# trinamic-controller-dribbler.net
KiCad netlist of a schematic drawn in Altium Designer
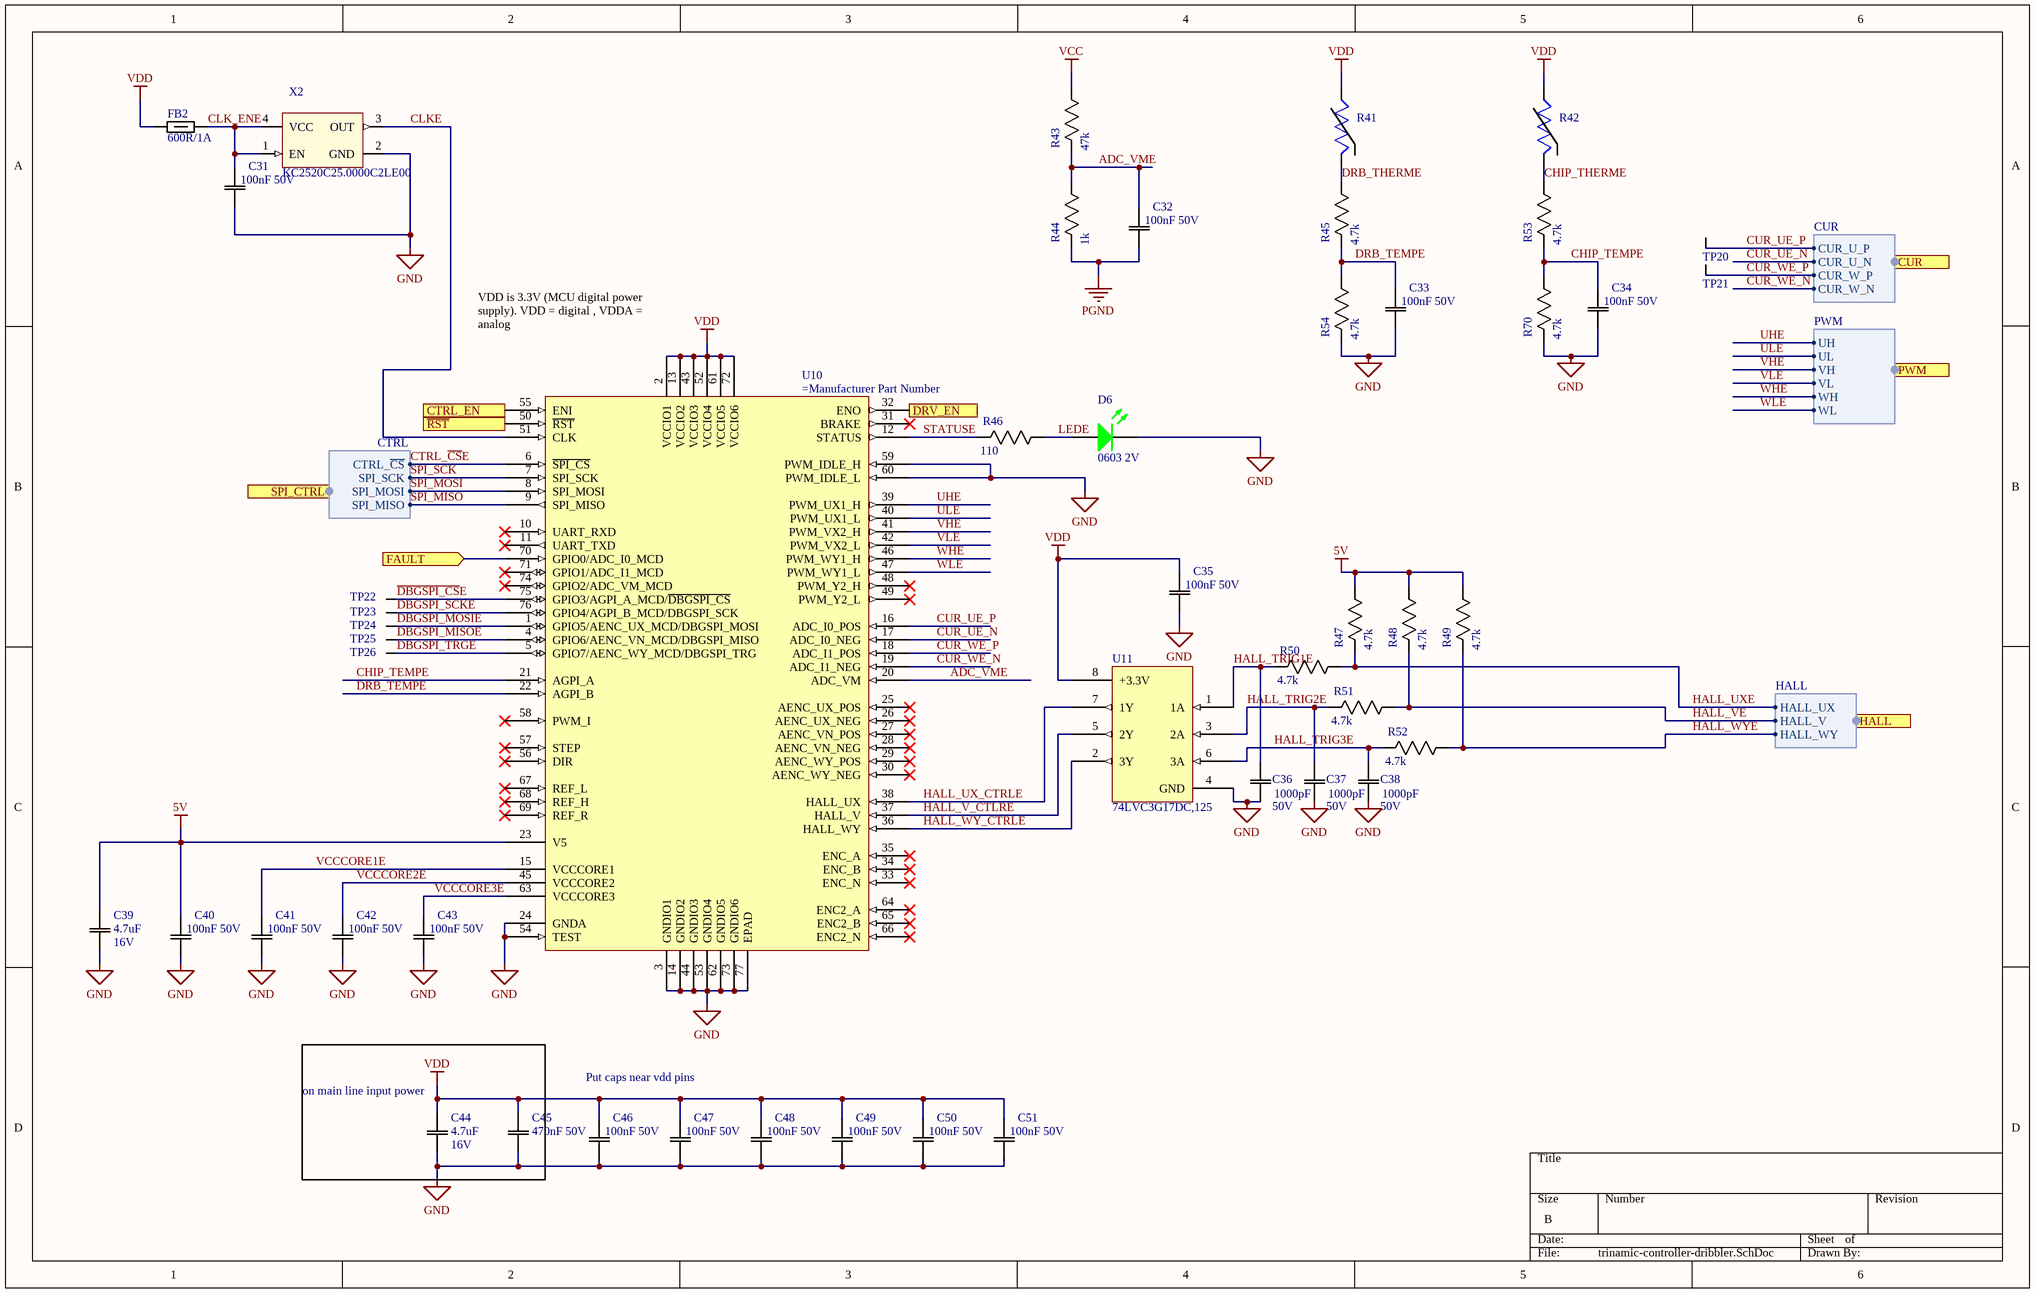
[diagram p0: trinamic-controller-dribbler.SchDoc]

(export (version "E")
  (design (tool "Eeschema 10.0.6"))
  (components
    (comp (ref "C31")
      (value "100nF 50V")
      (footprint "0603")
      (description "Default Symbol for Capacitors")
      (fields (field (name "TOLERANCE") "10%") (field (name "PART NUMBER") "CAP 100nF 50V"))
      (libsource (lib "capacitor_library") (part "CAP_Default"))
    )
    (comp (ref "C32")
      (value "100nF 50V")
      (footprint "0603")
      (description "Default Symbol for Capacitors")
      (fields (field (name "TOLERANCE") "10%") (field (name "PART NUMBER") "CAP 100nF 50V"))
      (libsource (lib "capacitor_library") (part "CAP_Default"))
    )
    (comp (ref "C33")
      (value "100nF 50V")
      (footprint "0603")
      (description "Default Symbol for Capacitors")
      (fields (field (name "TOLERANCE") "10%") (field (name "PART NUMBER") "CAP 100nF 50V"))
      (libsource (lib "capacitor_library") (part "CAP_Default"))
    )
    (comp (ref "C34")
      (value "100nF 50V")
      (footprint "0603")
      (description "Default Symbol for Capacitors")
      (fields (field (name "TOLERANCE") "10%") (field (name "PART NUMBER") "CAP 100nF 50V"))
      (libsource (lib "capacitor_library") (part "CAP_Default"))
    )
    (comp (ref "C35")
      (value "100nF 50V")
      (footprint "0603")
      (description "Default Symbol for Capacitors")
      (fields (field (name "TOLERANCE") "10%") (field (name "PART NUMBER") "CAP 100nF 50V"))
      (libsource (lib "capacitor_library") (part "CAP_Default"))
    )
    (comp (ref "C36")
      (value "1000pF")
      (footprint "0603")
      (description "Default Symbol for Capacitors")
      (fields
        (field (name "TOLERANCE") "10%")
        (field (name "RATING") "50V")
        (field (name "PART NUMBER") "CAP 1000pF 50V")
      )
      (libsource (lib "capacitor_library") (part "CAP_Default"))
    )
    (comp (ref "C37")
      (value "1000pF")
      (footprint "0603")
      (description "Default Symbol for Capacitors")
      (fields
        (field (name "TOLERANCE") "10%")
        (field (name "RATING") "50V")
        (field (name "PART NUMBER") "CAP 1000pF 50V")
      )
      (libsource (lib "capacitor_library") (part "CAP_Default"))
    )
    (comp (ref "C38")
      (value "1000pF")
      (footprint "0603")
      (description "Default Symbol for Capacitors")
      (fields
        (field (name "TOLERANCE") "10%")
        (field (name "RATING") "50V")
        (field (name "PART NUMBER") "CAP 1000pF 50V")
      )
      (libsource (lib "capacitor_library") (part "CAP_Default"))
    )
    (comp (ref "C39")
      (value "4.7uF")
      (footprint "0603")
      (description "Default Symbol for Capacitors")
      (fields
        (field (name "TOLERANCE") "10%")
        (field (name "RATING") "16V")
        (field (name "PART NUMBER") "CAP 4.7uF 16V")
      )
      (libsource (lib "capacitor_library") (part "CAP_Default"))
    )
    (comp (ref "C40")
      (value "100nF 50V")
      (footprint "0603")
      (description "Default Symbol for Capacitors")
      (fields (field (name "TOLERANCE") "10%") (field (name "PART NUMBER") "CAP 100nF 50V"))
      (libsource (lib "capacitor_library") (part "CAP_Default"))
    )
    (comp (ref "C41")
      (value "100nF 50V")
      (footprint "0603")
      (description "Default Symbol for Capacitors")
      (fields (field (name "TOLERANCE") "10%") (field (name "PART NUMBER") "CAP 100nF 50V"))
      (libsource (lib "capacitor_library") (part "CAP_Default"))
    )
    (comp (ref "C42")
      (value "100nF 50V")
      (footprint "0603")
      (description "Default Symbol for Capacitors")
      (fields (field (name "TOLERANCE") "10%") (field (name "PART NUMBER") "CAP 100nF 50V"))
      (libsource (lib "capacitor_library") (part "CAP_Default"))
    )
    (comp (ref "C43")
      (value "100nF 50V")
      (footprint "0603")
      (description "Default Symbol for Capacitors")
      (fields (field (name "TOLERANCE") "10%") (field (name "PART NUMBER") "CAP 100nF 50V"))
      (libsource (lib "capacitor_library") (part "CAP_Default"))
    )
    (comp (ref "C44")
      (value "4.7uF")
      (footprint "0603")
      (description "Default Symbol for Capacitors")
      (fields
        (field (name "TOLERANCE") "10%")
        (field (name "RATING") "16V")
        (field (name "PART NUMBER") "CAP 4.7uF 16V")
      )
      (libsource (lib "capacitor_library") (part "CAP_Default"))
    )
    (comp (ref "C45")
      (value "470nF 50V")
      (footprint "0603")
      (description "Default Symbol for Capacitors")
      (fields (field (name "TOLERANCE") "10%") (field (name "PART NUMBER") "CAP 470nF 50V"))
      (libsource (lib "capacitor_library") (part "CAP_Default"))
    )
    (comp (ref "C46")
      (value "100nF 50V")
      (footprint "0603")
      (description "Default Symbol for Capacitors")
      (fields (field (name "TOLERANCE") "10%") (field (name "PART NUMBER") "CAP 100nF 50V"))
      (libsource (lib "capacitor_library") (part "CAP_Default"))
    )
    (comp (ref "C47")
      (value "100nF 50V")
      (footprint "0603")
      (description "Default Symbol for Capacitors")
      (fields (field (name "TOLERANCE") "10%") (field (name "PART NUMBER") "CAP 100nF 50V"))
      (libsource (lib "capacitor_library") (part "CAP_Default"))
    )
    (comp (ref "C48")
      (value "100nF 50V")
      (footprint "0603")
      (description "Default Symbol for Capacitors")
      (fields (field (name "TOLERANCE") "10%") (field (name "PART NUMBER") "CAP 100nF 50V"))
      (libsource (lib "capacitor_library") (part "CAP_Default"))
    )
    (comp (ref "C49")
      (value "100nF 50V")
      (footprint "0603")
      (description "Default Symbol for Capacitors")
      (fields (field (name "TOLERANCE") "10%") (field (name "PART NUMBER") "CAP 100nF 50V"))
      (libsource (lib "capacitor_library") (part "CAP_Default"))
    )
    (comp (ref "C50")
      (value "100nF 50V")
      (footprint "0603")
      (description "Default Symbol for Capacitors")
      (fields (field (name "TOLERANCE") "10%") (field (name "PART NUMBER") "CAP 100nF 50V"))
      (libsource (lib "capacitor_library") (part "CAP_Default"))
    )
    (comp (ref "C51")
      (value "100nF 50V")
      (footprint "0603")
      (description "Default Symbol for Capacitors")
      (fields (field (name "TOLERANCE") "10%") (field (name "PART NUMBER") "CAP 100nF 50V"))
      (libsource (lib "capacitor_library") (part "CAP_Default"))
    )
    (comp (ref "D6")
      (value "0603 2V")
      (footprint "0603 - LED")
      (description "LED Uni-Color Green 574nm 2-Pin Chip LED T/R")
      (fields (field (name "PART NUMBER") "LED GREEN SMD 0603"))
      (libsource (lib "Diode_Library") (part "LED GREEN SMD 0603"))
    )
    (comp (ref "FB2")
      (value "600R/1A")
      (footprint "0603")
      (fields (field (name "PART NUMBER") "FERRITE BEAD 200 MOHM 0603 1LN"))
      (libsource (lib "Inductor_Library") (part "FERRITE BEAD 200 MOHM 0603 1LN"))
    )
    (comp (ref "R41")
      (value "RES NTC 10k")
      (footprint "THERMISTOR TH")
      (fields (field (name "PART NUMBER") "RES NTC 10k TH") (field (name "TOLERANCE") "1%"))
      (libsource (lib "Resistor_Library") (part "RES NTC 10k"))
    )
    (comp (ref "R42")
      (value "RES NTC 10k")
      (footprint "0603")
      (fields (field (name "PART NUMBER") "RES NTC 10k CHIP") (field (name "TOLERANCE") "1%"))
      (libsource (lib "Resistor_Library") (part "RES NTC 10k"))
    )
    (comp (ref "R43")
      (value "47k")
      (footprint "0603")
      (description "Default Resistor Symbol")
      (fields (field (name "TOLERANCE") "1%") (field (name "PART NUMBER") "RES 47k 1/8W - 1%"))
      (libsource (lib "") (part "RES_DEFAULT_2"))
    )
    (comp (ref "R44")
      (value "1k")
      (footprint "0603")
      (description "Default Resistor Symbol")
      (fields (field (name "TOLERANCE") "1%") (field (name "PART NUMBER") "RES 1k 1/8W - 1%"))
      (libsource (lib "") (part "RES_DEFAULT_1"))
    )
    (comp (ref "R45")
      (value "4.7k")
      (footprint "0603")
      (description "Default Resistor Symbol")
      (fields (field (name "TOLERANCE") "1%") (field (name "PART NUMBER") "RES 4.7k 1/8W - 1%"))
      (libsource (lib "") (part "RES_DEFAULT_1"))
    )
    (comp (ref "R46")
      (value "110")
      (footprint "0603")
      (description "Default Resistor Symbol")
      (fields (field (name "TOLERANCE") "1%") (field (name "PART NUMBER") "RES 110.0 1/8W - 1%"))
      (libsource (lib "Resistor_Library") (part "RES_DEFAULT"))
    )
    (comp (ref "R47")
      (value "4.7k")
      (footprint "0603")
      (description "Default Resistor Symbol")
      (fields (field (name "TOLERANCE") "5%") (field (name "PART NUMBER") "RES 4.7k 1/8W - 5%"))
      (libsource (lib "Resistor_Library") (part "RES_DEFAULT"))
    )
    (comp (ref "R48")
      (value "4.7k")
      (footprint "0603")
      (description "Default Resistor Symbol")
      (fields (field (name "TOLERANCE") "5%") (field (name "PART NUMBER") "RES 4.7k 1/8W - 5%"))
      (libsource (lib "Resistor_Library") (part "RES_DEFAULT"))
    )
    (comp (ref "R49")
      (value "4.7k")
      (footprint "0603")
      (description "Default Resistor Symbol")
      (fields (field (name "TOLERANCE") "5%") (field (name "PART NUMBER") "RES 4.7k 1/8W - 5%"))
      (libsource (lib "") (part "RES_DEFAULT_1"))
    )
    (comp (ref "R50")
      (value "4.7k")
      (footprint "0603")
      (description "Default Resistor Symbol")
      (fields (field (name "TOLERANCE") "5%") (field (name "PART NUMBER") "RES 4.7k 1/8W - 5%"))
      (libsource (lib "Resistor_Library") (part "RES_DEFAULT"))
    )
    (comp (ref "R51")
      (value "4.7k")
      (footprint "0603")
      (description "Default Resistor Symbol")
      (fields (field (name "TOLERANCE") "5%") (field (name "PART NUMBER") "RES 4.7k 1/8W - 5%"))
      (libsource (lib "Resistor_Library") (part "RES_DEFAULT"))
    )
    (comp (ref "R52")
      (value "4.7k")
      (footprint "0603")
      (description "Default Resistor Symbol")
      (fields (field (name "TOLERANCE") "5%") (field (name "PART NUMBER") "RES 4.7k 1/8W - 5%"))
      (libsource (lib "Resistor_Library") (part "RES_DEFAULT"))
    )
    (comp (ref "R53")
      (value "4.7k")
      (footprint "0603")
      (description "Default Resistor Symbol")
      (fields (field (name "TOLERANCE") "1%") (field (name "PART NUMBER") "RES 4.7k 1/8W - 1%"))
      (libsource (lib "") (part "RES_DEFAULT_1"))
    )
    (comp (ref "R54")
      (value "4.7k")
      (footprint "0603")
      (description "Default Resistor Symbol")
      (fields (field (name "TOLERANCE") "1%") (field (name "PART NUMBER") "RES 4.7k 1/8W - 1%"))
      (libsource (lib "") (part "RES_DEFAULT_1"))
    )
    (comp (ref "R70")
      (value "4.7k")
      (footprint "0603")
      (description "Default Resistor Symbol")
      (fields (field (name "TOLERANCE") "1%") (field (name "PART NUMBER") "RES 4.7k 1/8W - 1%"))
      (libsource (lib "") (part "RES_DEFAULT_1"))
    )
    (comp (ref "TP20")
      (value "Test Point (Via)")
      (footprint "TP")
      (libsource (lib "IC_Library") (part "Test Point (Via)"))
    )
    (comp (ref "TP21")
      (value "Test Point (Via)")
      (footprint "TP")
      (libsource (lib "IC_Library") (part "Test Point (Via)"))
    )
    (comp (ref "TP22")
      (value "Test Point (Via)")
      (footprint "TP")
      (libsource (lib "IC_Library") (part "Test Point (Via)"))
    )
    (comp (ref "TP23")
      (value "Test Point (Via)")
      (footprint "TP")
      (libsource (lib "IC_Library") (part "Test Point (Via)"))
    )
    (comp (ref "TP24")
      (value "Test Point (Via)")
      (footprint "TP")
      (libsource (lib "IC_Library") (part "Test Point (Via)"))
    )
    (comp (ref "TP25")
      (value "Test Point (Via)")
      (footprint "TP")
      (libsource (lib "IC_Library") (part "Test Point (Via)"))
    )
    (comp (ref "TP26")
      (value "Test Point (Via)")
      (footprint "TP")
      (libsource (lib "IC_Library") (part "Test Point (Via)"))
    )
    (comp (ref "U10")
      (value "~")
      (footprint "QFN40P1050X650X90_HS-77N")
      (description "Motor Driver, -40 To 125Deg C Rohs Compliant: Yes")
      (fields (field (name "PART NUMBER") "TMC4671"))
      (libsource (lib "IC_Library") (part "TMC4671"))
    )
    (comp (ref "U11")
      (value "74LVC3G17DC,125")
      (footprint "8-VSSOP")
      (description "IC BUFFER TRIPLE SCHMITT TRIGGER 5.5V VSSOP-8")
      (fields (field (name "PART NUMBER") "IC 74LVC3G17DC,125"))
      (libsource (lib "IC_Library") (part "IC 74LVC3G17DC,125"))
    )
    (comp (ref "X2")
      (value "KC2520C25.0000C2LE00")
      (footprint "KC2520C25.0000C2LE00")
      (description "Oscillator XO 25MHz ±15ppm 15pF CMOS 55% 2.5V/3.3V 4-Pin Mini-CSMD T/R")
      (fields (field (name "PART NUMBER") "XTAL OSC 25MHz 3.3V"))
      (libsource (lib "Oscillator_Library") (part "XTAL OSC 25MHz 3.3V"))
    )
  )
  (nets
    (net (code "5") (name "/ADC_VME") (class "Default")
      (node (ref "C32") (pin "2") (pinfunction "C2_2") (pintype "passive"))
      (node (ref "R43") (pin "2") (pinfunction "R2_2") (pintype "passive"))
      (node (ref "R44") (pin "1") (pinfunction "R1_1") (pintype "passive"))
      (node (ref "U10") (pin "20") (pinfunction "ADC_VM_20") (pintype "input"))
    )
    (net (code "6") (name "/CHIP_TEMPE") (class "Default")
      (node (ref "C34") (pin "2") (pinfunction "C2_2") (pintype "passive"))
      (node (ref "R53") (pin "2") (pinfunction "R2_2") (pintype "passive"))
      (node (ref "R70") (pin "1") (pinfunction "R1_1") (pintype "passive"))
      (node (ref "U10") (pin "21") (pinfunction "AGPI_A_21") (pintype "input"))
    )
    (net (code "7") (name "/CHIP_THERME") (class "Default")
      (node (ref "R42") (pin "1") (pinfunction "1_1") (pintype "passive"))
      (node (ref "R53") (pin "1") (pinfunction "R1_1") (pintype "passive"))
    )
    (net (code "8") (name "/CLKE") (class "Default")
      (node (ref "U10") (pin "51") (pinfunction "CLK_51") (pintype "input"))
      (node (ref "X2") (pin "3") (pinfunction "OUT_3") (pintype "output"))
    )
    (net (code "9") (name "/CLK_ENE") (class "Default")
      (node (ref "C31") (pin "2") (pinfunction "C2_2") (pintype "passive"))
      (node (ref "FB2") (pin "2") (pinfunction "2_2") (pintype "passive"))
      (node (ref "X2") (pin "1") (pinfunction "EN_1") (pintype "input"))
      (node (ref "X2") (pin "4") (pinfunction "VCC_4") (pintype "power_in"))
    )
    (net (code "10") (name "/CTRL_EN") (class "Default")
      (node (ref "U10") (pin "55") (pinfunction "ENI_55") (pintype "input"))
    )
    (net (code "11") (name "/CTRL_~{CS}E") (class "Default")
      (node (ref "U10") (pin "6") (pinfunction "~{SPI_CS}_6") (pintype "input"))
    )
    (net (code "12") (name "/CUR_UE_N") (class "Default")
      (node (ref "U10") (pin "17") (pinfunction "ADC_I0_NEG_17") (pintype "input"))
    )
    (net (code "13") (name "/CUR_UE_P") (class "Default")
      (node (ref "TP20") (pin "1") (pinfunction "1_1") (pintype "passive"))
      (node (ref "U10") (pin "16") (pinfunction "ADC_I0_POS_16") (pintype "input"))
    )
    (net (code "14") (name "/CUR_WE_N") (class "Default")
      (node (ref "U10") (pin "19") (pinfunction "ADC_I1_NEG_19") (pintype "input"))
    )
    (net (code "15") (name "/CUR_WE_P") (class "Default")
      (node (ref "TP21") (pin "1") (pinfunction "1_1") (pintype "passive"))
      (node (ref "U10") (pin "18") (pinfunction "ADC_I1_POS_18") (pintype "input"))
    )
    (net (code "16") (name "/DBGSPI_MISOE") (class "Default")
      (node (ref "TP25") (pin "1") (pinfunction "1_1") (pintype "passive"))
      (node (ref "U10") (pin "4") (pinfunction "GPIO6/AENC_VN_MCD/DBGSPI_MISO_4") (pintype "bidirectional"))
    )
    (net (code "17") (name "/DBGSPI_MOSIE") (class "Default")
      (node (ref "TP24") (pin "1") (pinfunction "1_1") (pintype "passive"))
      (node (ref "U10") (pin "1") (pinfunction "GPIO5/AENC_UX_MCD/DBGSPI_MOSI_1") (pintype "bidirectional"))
    )
    (net (code "18") (name "/DBGSPI_SCKE") (class "Default")
      (node (ref "TP23") (pin "1") (pinfunction "1_1") (pintype "passive"))
      (node (ref "U10") (pin "76") (pinfunction "GPIO4/AGPI_B_MCD/DBGSPI_SCK_76") (pintype "bidirectional"))
    )
    (net (code "19") (name "/DBGSPI_TRGE") (class "Default")
      (node (ref "TP26") (pin "1") (pinfunction "1_1") (pintype "passive"))
      (node (ref "U10") (pin "5") (pinfunction "GPIO7/AENC_WY_MCD/DBGSPI_TRG_5") (pintype "bidirectional"))
    )
    (net (code "20") (name "/DRB_TEMPE") (class "Default")
      (node (ref "C33") (pin "2") (pinfunction "C2_2") (pintype "passive"))
      (node (ref "R45") (pin "2") (pinfunction "R2_2") (pintype "passive"))
      (node (ref "R54") (pin "1") (pinfunction "R1_1") (pintype "passive"))
      (node (ref "U10") (pin "22") (pinfunction "AGPI_B_22") (pintype "input"))
    )
    (net (code "21") (name "/DRB_THERME") (class "Default")
      (node (ref "R41") (pin "1") (pinfunction "1_1") (pintype "passive"))
      (node (ref "R45") (pin "1") (pinfunction "R1_1") (pintype "passive"))
    )
    (net (code "22") (name "/DRV_EN") (class "Default")
      (node (ref "U10") (pin "32") (pinfunction "ENO_32") (pintype "output"))
    )
    (net (code "23") (name "/FAULT") (class "Default")
      (node (ref "U10") (pin "70") (pinfunction "GPIO0/ADC_I0_MCD_70") (pintype "input"))
    )
    (net (code "24") (name "/HALL_TRIG1E") (class "Default")
      (node (ref "C36") (pin "2") (pinfunction "C2_2") (pintype "passive"))
      (node (ref "R50") (pin "2") (pinfunction "R2_2") (pintype "passive"))
      (node (ref "U11") (pin "1") (pinfunction "1A_1") (pintype "input"))
    )
    (net (code "25") (name "/HALL_TRIG2E") (class "Default")
      (node (ref "C37") (pin "2") (pinfunction "C2_2") (pintype "passive"))
      (node (ref "R51") (pin "2") (pinfunction "R2_2") (pintype "passive"))
      (node (ref "U11") (pin "3") (pinfunction "2A_3") (pintype "input"))
    )
    (net (code "26") (name "/HALL_TRIG3E") (class "Default")
      (node (ref "C38") (pin "2") (pinfunction "C2_2") (pintype "passive"))
      (node (ref "R52") (pin "2") (pinfunction "R2_2") (pintype "passive"))
      (node (ref "U11") (pin "6") (pinfunction "3A_6") (pintype "input"))
    )
    (net (code "27") (name "/HALL_UXE") (class "Default")
      (node (ref "R47") (pin "2") (pinfunction "R2_2") (pintype "passive"))
      (node (ref "R50") (pin "1") (pinfunction "R1_1") (pintype "passive"))
    )
    (net (code "28") (name "/HALL_UX_CTRLE") (class "Default")
      (node (ref "U10") (pin "38") (pinfunction "HALL_UX_38") (pintype "input"))
      (node (ref "U11") (pin "7") (pinfunction "1Y_7") (pintype "output"))
    )
    (net (code "29") (name "/HALL_VE") (class "Default")
      (node (ref "R48") (pin "2") (pinfunction "R2_2") (pintype "passive"))
      (node (ref "R51") (pin "1") (pinfunction "R1_1") (pintype "passive"))
    )
    (net (code "30") (name "/HALL_V_CTLRE") (class "Default")
      (node (ref "U10") (pin "37") (pinfunction "HALL_V_37") (pintype "input"))
      (node (ref "U11") (pin "5") (pinfunction "2Y_5") (pintype "output"))
    )
    (net (code "31") (name "/HALL_WYE") (class "Default")
      (node (ref "R49") (pin "2") (pinfunction "R2_2") (pintype "passive"))
      (node (ref "R52") (pin "1") (pinfunction "R1_1") (pintype "passive"))
    )
    (net (code "32") (name "/HALL_WY_CTRLE") (class "Default")
      (node (ref "U10") (pin "36") (pinfunction "HALL_WY_36") (pintype "input"))
      (node (ref "U11") (pin "2") (pinfunction "3Y_2") (pintype "output"))
    )
    (net (code "33") (name "/LEDE") (class "Default")
      (node (ref "D6") (pin "1") (pinfunction "A_1") (pintype "passive"))
      (node (ref "R46") (pin "1") (pinfunction "R1_1") (pintype "passive"))
    )
    (net (code "34") (name "/SPI_MISO") (class "Default")
      (node (ref "U10") (pin "9") (pinfunction "SPI_MISO_9") (pintype "output"))
    )
    (net (code "35") (name "/SPI_MOSI") (class "Default")
      (node (ref "U10") (pin "8") (pinfunction "SPI_MOSI_8") (pintype "input"))
    )
    (net (code "36") (name "/SPI_SCK") (class "Default")
      (node (ref "U10") (pin "7") (pinfunction "SPI_SCK_7") (pintype "input"))
    )
    (net (code "37") (name "/STATUSE") (class "Default")
      (node (ref "R46") (pin "2") (pinfunction "R2_2") (pintype "passive"))
      (node (ref "U10") (pin "12") (pinfunction "STATUS_12") (pintype "output"))
    )
    (net (code "38") (name "/UHE") (class "Default")
      (node (ref "U10") (pin "39") (pinfunction "PWM_UX1_H_39") (pintype "output"))
    )
    (net (code "39") (name "/ULE") (class "Default")
      (node (ref "U10") (pin "40") (pinfunction "PWM_UX1_L_40") (pintype "output"))
    )
    (net (code "40") (name "/VCCCORE1E") (class "Default")
      (node (ref "C41") (pin "2") (pinfunction "C2_2") (pintype "passive"))
      (node (ref "U10") (pin "15") (pinfunction "VCCCORE1_15") (pintype "power_in"))
    )
    (net (code "41") (name "/VCCCORE2E") (class "Default")
      (node (ref "C42") (pin "2") (pinfunction "C2_2") (pintype "passive"))
      (node (ref "U10") (pin "45") (pinfunction "VCCCORE2_45") (pintype "power_in"))
    )
    (net (code "42") (name "/VCCCORE3E") (class "Default")
      (node (ref "C43") (pin "2") (pinfunction "C2_2") (pintype "passive"))
      (node (ref "U10") (pin "63") (pinfunction "VCCCORE3_63") (pintype "power_in"))
    )
    (net (code "43") (name "/VHE") (class "Default")
      (node (ref "U10") (pin "41") (pinfunction "PWM_VX2_H_41") (pintype "output"))
    )
    (net (code "44") (name "/VLE") (class "Default")
      (node (ref "U10") (pin "42") (pinfunction "PWM_VX2_L_42") (pintype "output"))
    )
    (net (code "45") (name "/WHE") (class "Default")
      (node (ref "U10") (pin "46") (pinfunction "PWM_WY1_H_46") (pintype "output"))
    )
    (net (code "46") (name "/WLE") (class "Default")
      (node (ref "U10") (pin "47") (pinfunction "PWM_WY1_L_47") (pintype "output"))
    )
    (net (code "51") (name "/~{DBGSPI_CS}E") (class "Default")
      (node (ref "TP22") (pin "1") (pinfunction "1_1") (pintype "passive"))
      (node (ref "U10") (pin "75") (pinfunction "GPIO3/AGPI_A_MCD/~{DBGSPI_CS}_75") (pintype "bidirectional"))
    )
    (net (code "52") (name "/~{RST}") (class "Default")
      (node (ref "U10") (pin "50") (pinfunction "~{RST}_50") (pintype "input"))
    )
    (net (code "53") (name "5V") (class "Default")
      (node (ref "C39") (pin "2") (pinfunction "C2_2") (pintype "passive"))
      (node (ref "C40") (pin "2") (pinfunction "C2_2") (pintype "passive"))
      (node (ref "R47") (pin "1") (pinfunction "R1_1") (pintype "passive"))
      (node (ref "R48") (pin "1") (pinfunction "R1_1") (pintype "passive"))
      (node (ref "R49") (pin "1") (pinfunction "R1_1") (pintype "passive"))
      (node (ref "U10") (pin "23") (pinfunction "V5_23") (pintype "power_in"))
    )
    (net (code "54") (name "GND") (class "Default")
      (node (ref "C31") (pin "1") (pinfunction "C1_1") (pintype "passive"))
      (node (ref "C33") (pin "1") (pinfunction "C1_1") (pintype "passive"))
      (node (ref "C34") (pin "1") (pinfunction "C1_1") (pintype "passive"))
      (node (ref "C35") (pin "1") (pinfunction "C1_1") (pintype "passive"))
      (node (ref "C36") (pin "1") (pinfunction "C1_1") (pintype "passive"))
      (node (ref "C37") (pin "1") (pinfunction "C1_1") (pintype "passive"))
      (node (ref "C38") (pin "1") (pinfunction "C1_1") (pintype "passive"))
      (node (ref "C39") (pin "1") (pinfunction "C1_1") (pintype "passive"))
      (node (ref "C40") (pin "1") (pinfunction "C1_1") (pintype "passive"))
      (node (ref "C41") (pin "1") (pinfunction "C1_1") (pintype "passive"))
      (node (ref "C42") (pin "1") (pinfunction "C1_1") (pintype "passive"))
      (node (ref "C43") (pin "1") (pinfunction "C1_1") (pintype "passive"))
      (node (ref "C44") (pin "1") (pinfunction "C1_1") (pintype "passive"))
      (node (ref "C45") (pin "1") (pinfunction "C1_1") (pintype "passive"))
      (node (ref "C46") (pin "1") (pinfunction "C1_1") (pintype "passive"))
      (node (ref "C47") (pin "1") (pinfunction "C1_1") (pintype "passive"))
      (node (ref "C48") (pin "1") (pinfunction "C1_1") (pintype "passive"))
      (node (ref "C49") (pin "1") (pinfunction "C1_1") (pintype "passive"))
      (node (ref "C50") (pin "1") (pinfunction "C1_1") (pintype "passive"))
      (node (ref "C51") (pin "1") (pinfunction "C1_1") (pintype "passive"))
      (node (ref "D6") (pin "2") (pinfunction "K_2") (pintype "passive"))
      (node (ref "R54") (pin "2") (pinfunction "R2_2") (pintype "passive"))
      (node (ref "R70") (pin "2") (pinfunction "R2_2") (pintype "passive"))
      (node (ref "U10") (pin "14") (pinfunction "GNDIO2_14") (pintype "power_in"))
      (node (ref "U10") (pin "24") (pinfunction "GNDA_24") (pintype "power_in"))
      (node (ref "U10") (pin "3") (pinfunction "GNDIO1_3") (pintype "power_in"))
      (node (ref "U10") (pin "44") (pinfunction "GNDIO3_44") (pintype "power_in"))
      (node (ref "U10") (pin "53") (pinfunction "GNDIO4_53") (pintype "power_in"))
      (node (ref "U10") (pin "54") (pinfunction "TEST_54") (pintype "input"))
      (node (ref "U10") (pin "59") (pinfunction "PWM_IDLE_H_59") (pintype "input"))
      (node (ref "U10") (pin "60") (pinfunction "PWM_IDLE_L_60") (pintype "input"))
      (node (ref "U10") (pin "62") (pinfunction "GNDIO5_62") (pintype "power_in"))
      (node (ref "U10") (pin "73") (pinfunction "GNDIO6_73") (pintype "power_in"))
      (node (ref "U10") (pin "77") (pinfunction "EPAD_77") (pintype "passive"))
      (node (ref "U11") (pin "4") (pinfunction "GND_4") (pintype "power_in"))
      (node (ref "X2") (pin "2") (pinfunction "GND_2") (pintype "power_in"))
    )
    (net (code "55") (name "PGND") (class "Default")
      (node (ref "C32") (pin "1") (pinfunction "C1_1") (pintype "passive"))
      (node (ref "R44") (pin "2") (pinfunction "R2_2") (pintype "passive"))
    )
    (net (code "56") (name "VCC") (class "Default")
      (node (ref "R43") (pin "1") (pinfunction "R1_1") (pintype "passive"))
    )
    (net (code "57") (name "VDD") (class "Default")
      (node (ref "C35") (pin "2") (pinfunction "C2_2") (pintype "passive"))
      (node (ref "C44") (pin "2") (pinfunction "C2_2") (pintype "passive"))
      (node (ref "C45") (pin "2") (pinfunction "C2_2") (pintype "passive"))
      (node (ref "C46") (pin "2") (pinfunction "C2_2") (pintype "passive"))
      (node (ref "C47") (pin "2") (pinfunction "C2_2") (pintype "passive"))
      (node (ref "C48") (pin "2") (pinfunction "C2_2") (pintype "passive"))
      (node (ref "C49") (pin "2") (pinfunction "C2_2") (pintype "passive"))
      (node (ref "C50") (pin "2") (pinfunction "C2_2") (pintype "passive"))
      (node (ref "C51") (pin "2") (pinfunction "C2_2") (pintype "passive"))
      (node (ref "FB2") (pin "1") (pinfunction "1_1") (pintype "passive"))
      (node (ref "R41") (pin "2") (pinfunction "2_2") (pintype "passive"))
      (node (ref "R42") (pin "2") (pinfunction "2_2") (pintype "passive"))
      (node (ref "U10") (pin "13") (pinfunction "VCCIO2_13") (pintype "power_in"))
      (node (ref "U10") (pin "2") (pinfunction "VCCIO1_2") (pintype "power_in"))
      (node (ref "U10") (pin "43") (pinfunction "VCCIO3_43") (pintype "power_in"))
      (node (ref "U10") (pin "52") (pinfunction "VCCIO4_52") (pintype "power_in"))
      (node (ref "U10") (pin "61") (pinfunction "VCCIO5_61") (pintype "power_in"))
      (node (ref "U10") (pin "72") (pinfunction "VCCIO6_72") (pintype "power_in"))
      (node (ref "U11") (pin "8") (pinfunction "+3.3V_8") (pintype "power_in"))
    )
    (net (code "58") (name "unconnected-(U10-AENC_UX_NEG-Pad26)") (class "Default")
      (node (ref "U10") (pin "26") (pinfunction "AENC_UX_NEG_26") (pintype "input+no_connect"))
    )
    (net (code "59") (name "unconnected-(U10-AENC_UX_POS-Pad25)") (class "Default")
      (node (ref "U10") (pin "25") (pinfunction "AENC_UX_POS_25") (pintype "input+no_connect"))
    )
    (net (code "60") (name "unconnected-(U10-AENC_VN_NEG-Pad28)") (class "Default")
      (node (ref "U10") (pin "28") (pinfunction "AENC_VN_NEG_28") (pintype "input+no_connect"))
    )
    (net (code "61") (name "unconnected-(U10-AENC_VN_POS-Pad27)") (class "Default")
      (node (ref "U10") (pin "27") (pinfunction "AENC_VN_POS_27") (pintype "input+no_connect"))
    )
    (net (code "62") (name "unconnected-(U10-AENC_WY_NEG-Pad30)") (class "Default")
      (node (ref "U10") (pin "30") (pinfunction "AENC_WY_NEG_30") (pintype "input+no_connect"))
    )
    (net (code "63") (name "unconnected-(U10-AENC_WY_POS-Pad29)") (class "Default")
      (node (ref "U10") (pin "29") (pinfunction "AENC_WY_POS_29") (pintype "input+no_connect"))
    )
    (net (code "64") (name "unconnected-(U10-BRAKE-Pad31)") (class "Default")
      (node (ref "U10") (pin "31") (pinfunction "BRAKE_31") (pintype "output+no_connect"))
    )
    (net (code "65") (name "unconnected-(U10-DIR-Pad56)") (class "Default")
      (node (ref "U10") (pin "56") (pinfunction "DIR_56") (pintype "input+no_connect"))
    )
    (net (code "66") (name "unconnected-(U10-ENC2_A-Pad64)") (class "Default")
      (node (ref "U10") (pin "64") (pinfunction "ENC2_A_64") (pintype "input+no_connect"))
    )
    (net (code "67") (name "unconnected-(U10-ENC2_B-Pad65)") (class "Default")
      (node (ref "U10") (pin "65") (pinfunction "ENC2_B_65") (pintype "input+no_connect"))
    )
    (net (code "68") (name "unconnected-(U10-ENC2_N-Pad66)") (class "Default")
      (node (ref "U10") (pin "66") (pinfunction "ENC2_N_66") (pintype "input+no_connect"))
    )
    (net (code "69") (name "unconnected-(U10-ENC_A-Pad35)") (class "Default")
      (node (ref "U10") (pin "35") (pinfunction "ENC_A_35") (pintype "input+no_connect"))
    )
    (net (code "70") (name "unconnected-(U10-ENC_B-Pad34)") (class "Default")
      (node (ref "U10") (pin "34") (pinfunction "ENC_B_34") (pintype "input+no_connect"))
    )
    (net (code "71") (name "unconnected-(U10-ENC_N-Pad33)") (class "Default")
      (node (ref "U10") (pin "33") (pinfunction "ENC_N_33") (pintype "input+no_connect"))
    )
    (net (code "72") (name "unconnected-(U10-GPIO1{slash}ADC_I1_MCD-Pad71)") (class "Default")
      (node (ref "U10") (pin "71") (pinfunction "GPIO1/ADC_I1_MCD_71") (pintype "bidirectional+no_connect"))
    )
    (net (code "73") (name "unconnected-(U10-GPIO2{slash}ADC_VM_MCD-Pad74)") (class "Default")
      (node (ref "U10") (pin "74") (pinfunction "GPIO2/ADC_VM_MCD_74") (pintype "bidirectional+no_connect"))
    )
    (net (code "74") (name "unconnected-(U10-PWM_I-Pad58)") (class "Default")
      (node (ref "U10") (pin "58") (pinfunction "PWM_I_58") (pintype "input+no_connect"))
    )
    (net (code "75") (name "unconnected-(U10-PWM_Y2_H-Pad48)") (class "Default")
      (node (ref "U10") (pin "48") (pinfunction "PWM_Y2_H_48") (pintype "output+no_connect"))
    )
    (net (code "76") (name "unconnected-(U10-PWM_Y2_L-Pad49)") (class "Default")
      (node (ref "U10") (pin "49") (pinfunction "PWM_Y2_L_49") (pintype "output+no_connect"))
    )
    (net (code "77") (name "unconnected-(U10-REF_H-Pad68)") (class "Default")
      (node (ref "U10") (pin "68") (pinfunction "REF_H_68") (pintype "input+no_connect"))
    )
    (net (code "78") (name "unconnected-(U10-REF_L-Pad67)") (class "Default")
      (node (ref "U10") (pin "67") (pinfunction "REF_L_67") (pintype "input+no_connect"))
    )
    (net (code "79") (name "unconnected-(U10-REF_R-Pad69)") (class "Default")
      (node (ref "U10") (pin "69") (pinfunction "REF_R_69") (pintype "input+no_connect"))
    )
    (net (code "80") (name "unconnected-(U10-STEP-Pad57)") (class "Default")
      (node (ref "U10") (pin "57") (pinfunction "STEP_57") (pintype "input+no_connect"))
    )
    (net (code "81") (name "unconnected-(U10-UART_RXD-Pad10)") (class "Default")
      (node (ref "U10") (pin "10") (pinfunction "UART_RXD_10") (pintype "input+no_connect"))
    )
    (net (code "82") (name "unconnected-(U10-UART_TXD-Pad11)") (class "Default")
      (node (ref "U10") (pin "11") (pinfunction "UART_TXD_11") (pintype "output+no_connect"))
    )
  )
)
